# Millable_AK9750_Human_Movement_Sensor_Br.net
KiCad netlist of a schematic drawn in EAGLE
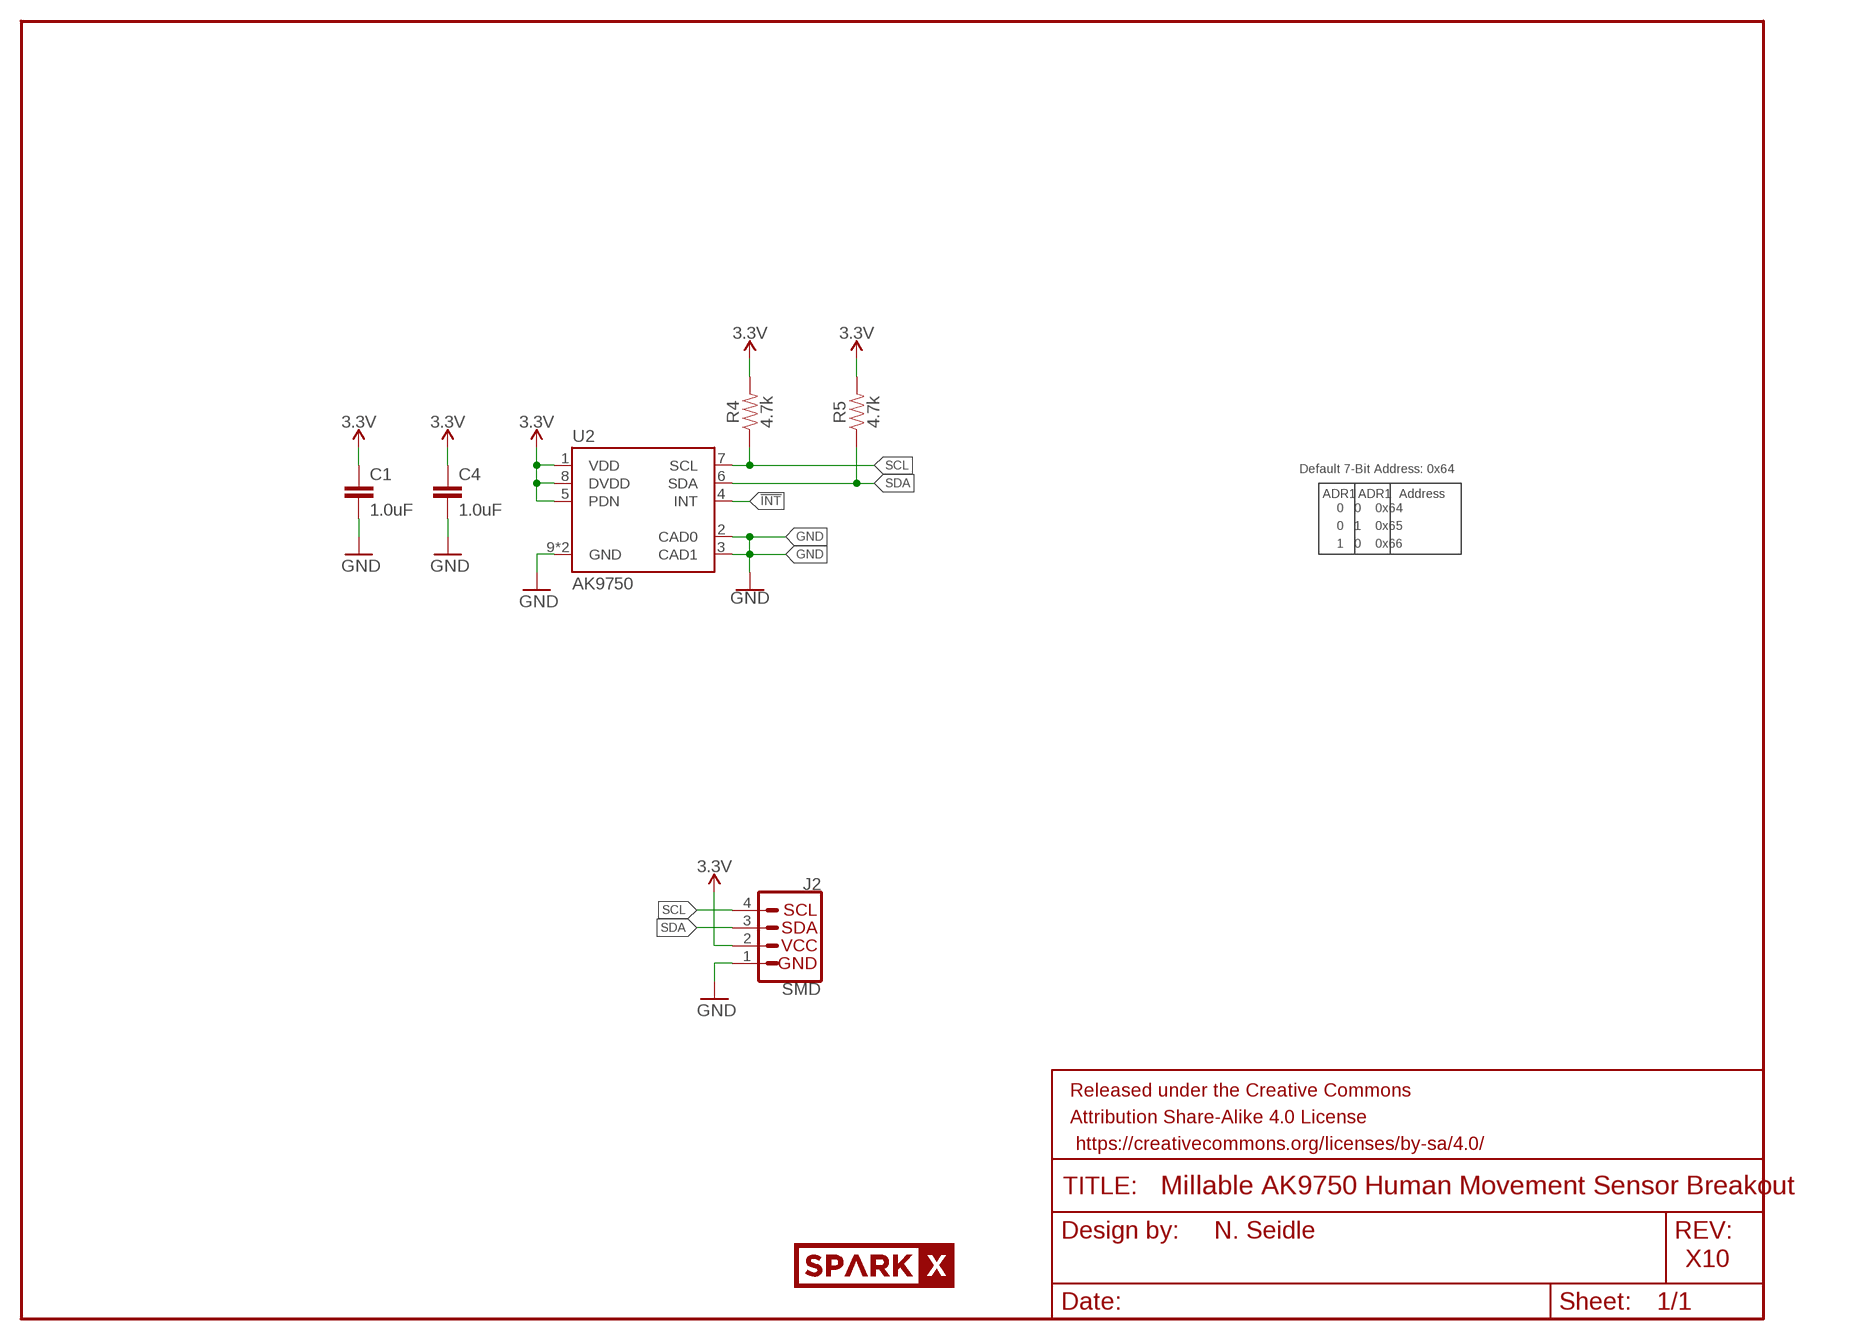
[diagram p0: schematic, sheet 1]

(export (version "E")
  (design (tool "Eeschema 10.0.6"))
  (components
    (comp (ref "C1")
      (value "1.0uF")
      (footprint "eagle-import:0603")
      (libsource (lib "eagle-import") (part "1.0UF-0603-16V-10%"))
    )
    (comp (ref "C4")
      (value "1.0uF")
      (footprint "eagle-import:0603")
      (libsource (lib "eagle-import") (part "1.0UF-0603-16V-10%"))
    )
    (comp (ref "FRAME1")
      (value "FRAME-LETTER")
      (footprint "eagle-import:CREATIVE_COMMONS")
      (libsource (lib "eagle-import") (part "FRAME-LETTER"))
    )
    (comp (ref "J2")
      (value "SMD")
      (footprint "eagle-import:1X04_1MM_RA")
      (libsource (lib "eagle-import") (part "I2C_STANDARDJS-1MM"))
    )
    (comp (ref "R4")
      (value "4.7k")
      (footprint "eagle-import:0603")
      (libsource (lib "eagle-import") (part "4.7KOHM-0603-1/10W-1%"))
    )
    (comp (ref "R5")
      (value "4.7k")
      (footprint "eagle-import:0603")
      (libsource (lib "eagle-import") (part "4.7KOHM-0603-1/10W-1%"))
    )
    (comp (ref "U$2")
      (value "SPARKX-LOGO4")
      (footprint "eagle-import:SPARKX-MEDIUM")
      (libsource (lib "eagle-import") (part "SPARKX-LOGO4"))
    )
    (comp (ref "U2")
      (value "AK9750")
      (footprint "eagle-import:SON10")
      (libsource (lib "eagle-import") (part "AK9750"))
    )
  )
  (nets
    (net (code "1") (name "/~{INT}") (class "Default")
      (node (ref "U2") (pin "4") (pinfunction "INT_4") (pintype "bidirectional"))
    )
    (net (code "2") (name "3.3V") (class "Default")
      (node (ref "C1") (pin "1") (pinfunction "1_1") (pintype "passive"))
      (node (ref "C4") (pin "1") (pinfunction "1_1") (pintype "passive"))
      (node (ref "J2") (pin "2") (pinfunction "VCC_2") (pintype "power_in"))
      (node (ref "R4") (pin "2") (pinfunction "2_2") (pintype "passive"))
      (node (ref "R5") (pin "2") (pinfunction "2_2") (pintype "passive"))
      (node (ref "U2") (pin "1") (pinfunction "VDD_1") (pintype "bidirectional"))
      (node (ref "U2") (pin "5") (pinfunction "PDN_5") (pintype "bidirectional"))
      (node (ref "U2") (pin "8") (pinfunction "DVDD_8") (pintype "bidirectional"))
    )
    (net (code "3") (name "GND") (class "Default")
      (node (ref "C1") (pin "2") (pinfunction "2_2") (pintype "passive"))
      (node (ref "C4") (pin "2") (pinfunction "2_2") (pintype "passive"))
      (node (ref "J2") (pin "1") (pinfunction "GND_1") (pintype "power_in"))
      (node (ref "U2") (pin "10") (pinfunction "GND_10") (pintype "bidirectional"))
      (node (ref "U2") (pin "2") (pinfunction "CAD0_2") (pintype "bidirectional"))
      (node (ref "U2") (pin "3") (pinfunction "CAD1_3") (pintype "bidirectional"))
      (node (ref "U2") (pin "9") (pinfunction "GND_9") (pintype "bidirectional"))
    )
    (net (code "4") (name "SCL") (class "Default")
      (node (ref "J2") (pin "4") (pinfunction "SCL_4") (pintype "passive"))
      (node (ref "R4") (pin "1") (pinfunction "1_1") (pintype "passive"))
      (node (ref "U2") (pin "7") (pinfunction "SCL_7") (pintype "bidirectional"))
    )
    (net (code "5") (name "SDA") (class "Default")
      (node (ref "J2") (pin "3") (pinfunction "SDA_3") (pintype "passive"))
      (node (ref "R5") (pin "1") (pinfunction "1_1") (pintype "passive"))
      (node (ref "U2") (pin "6") (pinfunction "SDA_6") (pintype "bidirectional"))
    )
  )
)
